# ssr_board.net
KiCad netlist of a schematic drawn in EAGLE
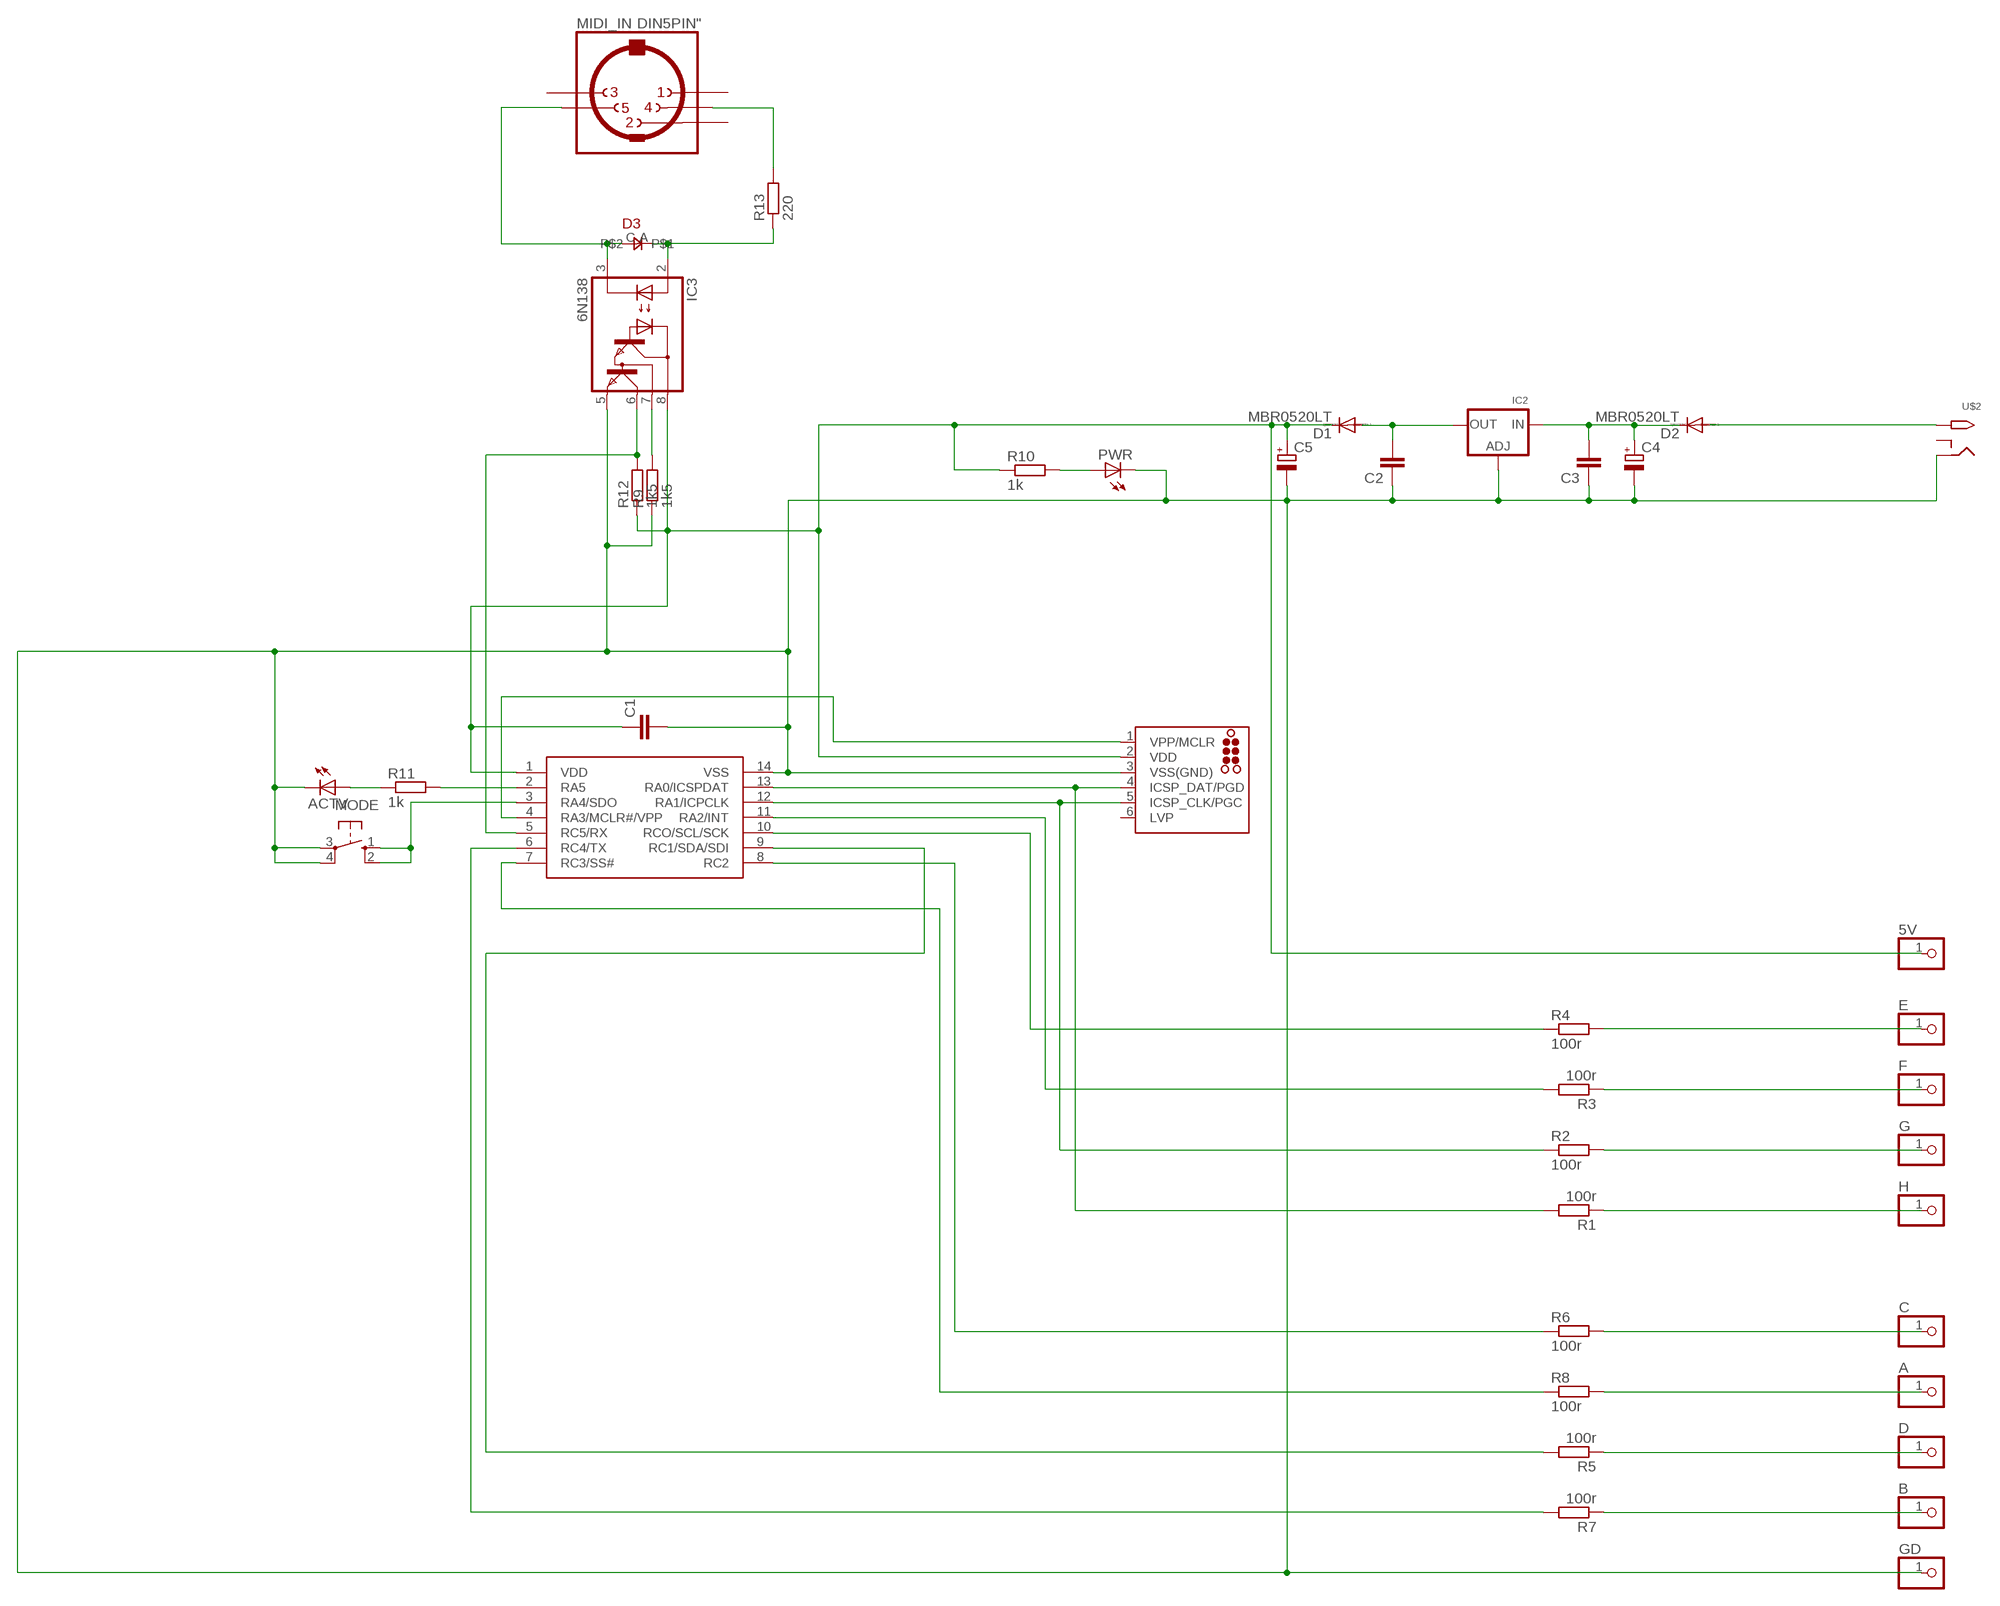
[diagram p0: schematic, sheet 1]

(export (version "E")
  (design (tool "Eeschema 10.0.6"))
  (components
    (comp (ref "5V")
      (value "PINHD-1X1")
      (footprint "eagle-import:1X01")
      (libsource (lib "eagle-import") (part "PINHD-1X1"))
    )
    (comp (ref "A")
      (value "PINHD-1X1")
      (footprint "eagle-import:1X01")
      (libsource (lib "eagle-import") (part "PINHD-1X1"))
    )
    (comp (ref "ACTV")
      (value "LED3MM")
      (footprint "eagle-import:LED3MM")
      (libsource (lib "eagle-import") (part "LED3MM"))
    )
    (comp (ref "B")
      (value "PINHD-1X1")
      (footprint "eagle-import:1X01")
      (libsource (lib "eagle-import") (part "PINHD-1X1"))
    )
    (comp (ref "C")
      (value "PINHD-1X1")
      (footprint "eagle-import:1X01")
      (libsource (lib "eagle-import") (part "PINHD-1X1"))
    )
    (comp (ref "C1")
      (value "C-EUC0805")
      (footprint "eagle-import:C0805")
      (libsource (lib "eagle-import") (part "C-EUC0805"))
    )
    (comp (ref "C2")
      (value "C-EUC0805")
      (footprint "eagle-import:C0805")
      (libsource (lib "eagle-import") (part "C-EUC0805"))
    )
    (comp (ref "C3")
      (value "C-EUC0805")
      (footprint "eagle-import:C0805")
      (libsource (lib "eagle-import") (part "C-EUC0805"))
    )
    (comp (ref "C4")
      (value "CPOL-EUE2-5")
      (footprint "eagle-import:E2-5")
      (libsource (lib "eagle-import") (part "CPOL-EUE2-5"))
    )
    (comp (ref "C5")
      (value "CPOL-EUE2-5")
      (footprint "eagle-import:E2-5")
      (libsource (lib "eagle-import") (part "CPOL-EUE2-5"))
    )
    (comp (ref "D")
      (value "PINHD-1X1")
      (footprint "eagle-import:1X01")
      (libsource (lib "eagle-import") (part "PINHD-1X1"))
    )
    (comp (ref "D1")
      (value "MBR0520LT")
      (footprint "eagle-import:SOD123")
      (libsource (lib "eagle-import") (part "MBR0520LT"))
    )
    (comp (ref "D2")
      (value "MBR0520LT")
      (footprint "eagle-import:SOD123")
      (libsource (lib "eagle-import") (part "MBR0520LT"))
    )
    (comp (ref "D3")
      (value "0805DIODE")
      (footprint "eagle-import:0805DIODE")
      (libsource (lib "eagle-import") (part "0805DIODE"))
    )
    (comp (ref "E")
      (value "PINHD-1X1")
      (footprint "eagle-import:1X01")
      (libsource (lib "eagle-import") (part "PINHD-1X1"))
    )
    (comp (ref "F")
      (value "PINHD-1X1")
      (footprint "eagle-import:1X01")
      (libsource (lib "eagle-import") (part "PINHD-1X1"))
    )
    (comp (ref "G")
      (value "PINHD-1X1")
      (footprint "eagle-import:1X01")
      (libsource (lib "eagle-import") (part "PINHD-1X1"))
    )
    (comp (ref "GD")
      (value "PINHD-1X1")
      (footprint "eagle-import:1X01")
      (libsource (lib "eagle-import") (part "PINHD-1X1"))
    )
    (comp (ref "H")
      (value "PINHD-1X1")
      (footprint "eagle-import:1X01")
      (libsource (lib "eagle-import") (part "PINHD-1X1"))
    )
    (comp (ref "IC1")
      (value "PIC16F1825SO14")
      (footprint "eagle-import:SO14")
      (libsource (lib "eagle-import") (part "PIC16F1825SO14"))
    )
    (comp (ref "IC2")
      (value "LM1117SOT223-WAVE")
      (footprint "eagle-import:SOT223-W")
      (libsource (lib "eagle-import") (part "LM1117SOT223-WAVE"))
    )
    (comp (ref "IC3")
      (value "6N138")
      (footprint "eagle-import:DIL08")
      (libsource (lib "eagle-import") (part "6N138"))
    )
    (comp (ref "ICSP")
      (value "TC2030-MCP-NL")
      (footprint "eagle-import:TC2030-MCP-NL")
      (libsource (lib "eagle-import") (part "TC2030-MCP-NL"))
    )
    (comp (ref "MIDI_IN")
      (value "DIN5PIN\"")
      (footprint "eagle-import:TRUCONN90")
      (libsource (lib "eagle-import") (part "DIN5PIN{dblquote}"))
    )
    (comp (ref "MODE")
      (value "10-XX")
      (footprint "eagle-import:B3F-10XX")
      (libsource (lib "eagle-import") (part "10-XX"))
    )
    (comp (ref "PWR")
      (value "LED3MM")
      (footprint "eagle-import:LED3MM")
      (libsource (lib "eagle-import") (part "LED3MM"))
    )
    (comp (ref "R1")
      (value "100r")
      (footprint "eagle-import:R0805")
      (libsource (lib "eagle-import") (part "R-EU_R0805"))
    )
    (comp (ref "R2")
      (value "100r")
      (footprint "eagle-import:R0805")
      (libsource (lib "eagle-import") (part "R-EU_R0805"))
    )
    (comp (ref "R3")
      (value "100r")
      (footprint "eagle-import:R0805")
      (libsource (lib "eagle-import") (part "R-EU_R0805"))
    )
    (comp (ref "R4")
      (value "100r")
      (footprint "eagle-import:R0805")
      (libsource (lib "eagle-import") (part "R-EU_R0805"))
    )
    (comp (ref "R5")
      (value "100r")
      (footprint "eagle-import:R0805")
      (libsource (lib "eagle-import") (part "R-EU_R0805"))
    )
    (comp (ref "R6")
      (value "100r")
      (footprint "eagle-import:R0805")
      (libsource (lib "eagle-import") (part "R-EU_R0805"))
    )
    (comp (ref "R7")
      (value "100r")
      (footprint "eagle-import:R0805")
      (libsource (lib "eagle-import") (part "R-EU_R0805"))
    )
    (comp (ref "R8")
      (value "100r")
      (footprint "eagle-import:R0805")
      (libsource (lib "eagle-import") (part "R-EU_R0805"))
    )
    (comp (ref "R9")
      (value "1k5")
      (footprint "eagle-import:R0805")
      (libsource (lib "eagle-import") (part "R-EU_R0805"))
    )
    (comp (ref "R10")
      (value "1k")
      (footprint "eagle-import:R0805")
      (libsource (lib "eagle-import") (part "R-EU_R0805"))
    )
    (comp (ref "R11")
      (value "1k")
      (footprint "eagle-import:R0805")
      (libsource (lib "eagle-import") (part "R-EU_R0805"))
    )
    (comp (ref "R12")
      (value "1k5")
      (footprint "eagle-import:R0805")
      (libsource (lib "eagle-import") (part "R-EU_R0805"))
    )
    (comp (ref "R13")
      (value "220")
      (footprint "eagle-import:R0805")
      (libsource (lib "eagle-import") (part "R-EU_R0805"))
    )
    (comp (ref "U$2")
      (value "2.1MMJACKTHM")
      (footprint "eagle-import:PJ-102A")
      (libsource (lib "eagle-import") (part "2.1MMJACKTHM"))
    )
  )
  (nets
    (net (code "1") (name "Net-(A-Pad1)") (class "Default")
      (node (ref "A") (pin "1") (pinfunction "1_1") (pintype "passive"))
      (node (ref "R8") (pin "2") (pinfunction "2_2") (pintype "passive"))
    )
    (net (code "2") (name "Net-(ACTV-C)") (class "Default")
      (node (ref "ACTV") (pin "K") (pinfunction "C_K") (pintype "passive"))
      (node (ref "C1") (pin "2") (pinfunction "2_2") (pintype "passive"))
      (node (ref "C2") (pin "1") (pinfunction "1_1") (pintype "passive"))
      (node (ref "C3") (pin "1") (pinfunction "1_1") (pintype "passive"))
      (node (ref "C4") (pin "-") (pinfunction "-_-") (pintype "passive"))
      (node (ref "C5") (pin "-") (pinfunction "-_-") (pintype "passive"))
      (node (ref "GD") (pin "1") (pinfunction "1_1") (pintype "passive"))
      (node (ref "IC1") (pin "14") (pinfunction "VSS_14") (pintype "power_in"))
      (node (ref "IC2") (pin "1") (pinfunction "ADJ_1") (pintype "input"))
      (node (ref "IC3") (pin "5") (pinfunction "GND_5") (pintype "passive"))
      (node (ref "ICSP") (pin "3") (pinfunction "VSS(GND)_3") (pintype "power_in"))
      (node (ref "MODE") (pin "3") (pinfunction "P_3") (pintype "passive"))
      (node (ref "MODE") (pin "4") (pinfunction "P1_4") (pintype "passive"))
      (node (ref "PWR") (pin "K") (pinfunction "C_K") (pintype "passive"))
      (node (ref "R9") (pin "1") (pinfunction "1_1") (pintype "passive"))
      (node (ref "U$2") (pin "RING") (pinfunction "RING_RING") (pintype "bidirectional"))
    )
    (net (code "3") (name "Net-(ACTV-PadA)") (class "Default")
      (node (ref "ACTV") (pin "A") (pinfunction "A_A") (pintype "passive"))
      (node (ref "R11") (pin "1") (pinfunction "1_1") (pintype "passive"))
    )
    (net (code "4") (name "Net-(B-Pad1)") (class "Default")
      (node (ref "B") (pin "1") (pinfunction "1_1") (pintype "passive"))
      (node (ref "R7") (pin "1") (pinfunction "1_1") (pintype "passive"))
    )
    (net (code "5") (name "Net-(C-Pad1)") (class "Default")
      (node (ref "C") (pin "1") (pinfunction "1_1") (pintype "passive"))
      (node (ref "R6") (pin "2") (pinfunction "2_2") (pintype "passive"))
    )
    (net (code "6") (name "Net-(D-Pad1)") (class "Default")
      (node (ref "D") (pin "1") (pinfunction "1_1") (pintype "passive"))
      (node (ref "R5") (pin "1") (pinfunction "1_1") (pintype "passive"))
    )
    (net (code "7") (name "Net-(D2-PadA)") (class "Default")
      (node (ref "D2") (pin "A") (pinfunction "A_A") (pintype "passive"))
      (node (ref "U$2") (pin "TIP") (pinfunction "TIP_TIP") (pintype "bidirectional"))
    )
    (net (code "8") (name "Net-(D3-P$1)") (class "Default")
      (node (ref "D3") (pin "C") (pinfunction "P$1_C") (pintype "bidirectional"))
      (node (ref "IC3") (pin "3") (pinfunction "C_3") (pintype "passive"))
      (node (ref "MIDI_IN") (pin "5") (pinfunction "5_5") (pintype "passive"))
    )
    (net (code "9") (name "Net-(D3-P$2)") (class "Default")
      (node (ref "D3") (pin "A") (pinfunction "P$2_A") (pintype "bidirectional"))
      (node (ref "IC3") (pin "2") (pinfunction "A_2") (pintype "passive"))
      (node (ref "R13") (pin "1") (pinfunction "1_1") (pintype "passive"))
    )
    (net (code "10") (name "Net-(E-Pad1)") (class "Default")
      (node (ref "E") (pin "1") (pinfunction "1_1") (pintype "passive"))
      (node (ref "R4") (pin "2") (pinfunction "2_2") (pintype "passive"))
    )
    (net (code "11") (name "Net-(F-Pad1)") (class "Default")
      (node (ref "F") (pin "1") (pinfunction "1_1") (pintype "passive"))
      (node (ref "R3") (pin "1") (pinfunction "1_1") (pintype "passive"))
    )
    (net (code "12") (name "Net-(G-Pad1)") (class "Default")
      (node (ref "G") (pin "1") (pinfunction "1_1") (pintype "passive"))
      (node (ref "R2") (pin "2") (pinfunction "2_2") (pintype "passive"))
    )
    (net (code "13") (name "Net-(H-Pad1)") (class "Default")
      (node (ref "H") (pin "1") (pinfunction "1_1") (pintype "passive"))
      (node (ref "R1") (pin "1") (pinfunction "1_1") (pintype "passive"))
    )
    (net (code "14") (name "Net-(IC1-RA0{slash}ICSPDAT)") (class "Default")
      (node (ref "IC1") (pin "13") (pinfunction "RA0/ICSPDAT_13") (pintype "bidirectional"))
      (node (ref "ICSP") (pin "4") (pinfunction "ICSP_DAT/PGD_4") (pintype "bidirectional"))
      (node (ref "R1") (pin "2") (pinfunction "2_2") (pintype "passive"))
    )
    (net (code "15") (name "Net-(IC1-RA1{slash}ICPCLK)") (class "Default")
      (node (ref "IC1") (pin "12") (pinfunction "RA1/ICPCLK_12") (pintype "bidirectional"))
      (node (ref "ICSP") (pin "5") (pinfunction "ICSP_CLK/PGC_5") (pintype "output"))
      (node (ref "R2") (pin "1") (pinfunction "1_1") (pintype "passive"))
    )
    (net (code "16") (name "Net-(IC1-RA2{slash}INT)") (class "Default")
      (node (ref "IC1") (pin "11") (pinfunction "RA2/INT_11") (pintype "bidirectional"))
      (node (ref "R3") (pin "2") (pinfunction "2_2") (pintype "passive"))
    )
    (net (code "17") (name "Net-(IC1-RA3{slash}MCLR#{slash}VPP)") (class "Default")
      (node (ref "IC1") (pin "4") (pinfunction "RA3/MCLR#/VPP_4") (pintype "input"))
      (node (ref "ICSP") (pin "1") (pinfunction "VPP/MCLR_1") (pintype "passive"))
    )
    (net (code "18") (name "Net-(IC1-RA4{slash}SDO)") (class "Default")
      (node (ref "IC1") (pin "3") (pinfunction "RA4/SDO_3") (pintype "bidirectional"))
      (node (ref "MODE") (pin "1") (pinfunction "S_1") (pintype "passive"))
      (node (ref "MODE") (pin "2") (pinfunction "S1_2") (pintype "passive"))
    )
    (net (code "19") (name "Net-(IC1-RA5)") (class "Default")
      (node (ref "IC1") (pin "2") (pinfunction "RA5_2") (pintype "bidirectional"))
      (node (ref "R11") (pin "2") (pinfunction "2_2") (pintype "passive"))
    )
    (net (code "20") (name "Net-(IC1-RC1{slash}SDA{slash}SDI)") (class "Default")
      (node (ref "IC1") (pin "9") (pinfunction "RC1/SDA/SDI_9") (pintype "bidirectional"))
      (node (ref "R5") (pin "2") (pinfunction "2_2") (pintype "passive"))
    )
    (net (code "21") (name "Net-(IC1-RC2)") (class "Default")
      (node (ref "IC1") (pin "8") (pinfunction "RC2_8") (pintype "bidirectional"))
      (node (ref "R6") (pin "1") (pinfunction "1_1") (pintype "passive"))
    )
    (net (code "22") (name "Net-(IC1-RC3{slash}SS#)") (class "Default")
      (node (ref "IC1") (pin "7") (pinfunction "RC3/SS#_7") (pintype "bidirectional"))
      (node (ref "R8") (pin "1") (pinfunction "1_1") (pintype "passive"))
    )
    (net (code "23") (name "Net-(IC1-RC4{slash}TX)") (class "Default")
      (node (ref "IC1") (pin "6") (pinfunction "RC4/TX_6") (pintype "bidirectional"))
      (node (ref "R7") (pin "2") (pinfunction "2_2") (pintype "passive"))
    )
    (net (code "24") (name "Net-(IC1-RC5{slash}RX)") (class "Default")
      (node (ref "IC1") (pin "5") (pinfunction "RC5/RX_5") (pintype "bidirectional"))
      (node (ref "IC3") (pin "6") (pinfunction "VO_6") (pintype "passive"))
      (node (ref "R12") (pin "2") (pinfunction "2_2") (pintype "passive"))
    )
    (net (code "25") (name "Net-(IC1-RCO{slash}SCL{slash}SCK)") (class "Default")
      (node (ref "IC1") (pin "10") (pinfunction "RCO/SCL/SCK_10") (pintype "bidirectional"))
      (node (ref "R4") (pin "1") (pinfunction "1_1") (pintype "passive"))
    )
    (net (code "26") (name "Net-(IC1-VDD)") (class "Default")
      (node (ref "5V") (pin "1") (pinfunction "1_1") (pintype "passive"))
      (node (ref "C1") (pin "1") (pinfunction "1_1") (pintype "passive"))
      (node (ref "C5") (pin "+") (pinfunction "+_+") (pintype "passive"))
      (node (ref "D1") (pin "C") (pinfunction "C_C") (pintype "passive"))
      (node (ref "IC1") (pin "1") (pinfunction "VDD_1") (pintype "power_in"))
      (node (ref "IC3") (pin "8") (pinfunction "VCC_8") (pintype "passive"))
      (node (ref "ICSP") (pin "2") (pinfunction "VDD_2") (pintype "power_in"))
      (node (ref "R10") (pin "1") (pinfunction "1_1") (pintype "passive"))
      (node (ref "R12") (pin "1") (pinfunction "1_1") (pintype "passive"))
    )
    (net (code "27") (name "Net-(IC2-IN)") (class "Default")
      (node (ref "C3") (pin "2") (pinfunction "2_2") (pintype "passive"))
      (node (ref "C4") (pin "+") (pinfunction "+_+") (pintype "passive"))
      (node (ref "D2") (pin "C") (pinfunction "C_C") (pintype "passive"))
      (node (ref "IC2") (pin "3") (pinfunction "IN_3") (pintype "input"))
    )
    (net (code "28") (name "Net-(IC2-OUT)") (class "Default")
      (node (ref "C2") (pin "2") (pinfunction "2_2") (pintype "passive"))
      (node (ref "D1") (pin "A") (pinfunction "A_A") (pintype "passive"))
      (node (ref "IC2") (pin "2") (pinfunction "OUT_2") (pintype "passive"))
    )
    (net (code "29") (name "Net-(IC3-VB)") (class "Default")
      (node (ref "IC3") (pin "7") (pinfunction "VB_7") (pintype "passive"))
      (node (ref "R9") (pin "2") (pinfunction "2_2") (pintype "passive"))
    )
    (net (code "30") (name "Net-(MIDI_IN-Pad4)") (class "Default")
      (node (ref "MIDI_IN") (pin "4") (pinfunction "4_4") (pintype "passive"))
      (node (ref "R13") (pin "2") (pinfunction "2_2") (pintype "passive"))
    )
    (net (code "31") (name "Net-(PWR-PadA)") (class "Default")
      (node (ref "PWR") (pin "A") (pinfunction "A_A") (pintype "passive"))
      (node (ref "R10") (pin "2") (pinfunction "2_2") (pintype "passive"))
    )
    (net (code "32") (name "unconnected-(ICSP-LVP-Pad6)") (class "Default")
      (node (ref "ICSP") (pin "6") (pinfunction "LVP_6") (pintype "bidirectional"))
    )
    (net (code "33") (name "unconnected-(MIDI_IN-Pad1)") (class "Default")
      (node (ref "MIDI_IN") (pin "1") (pinfunction "1_1") (pintype "passive"))
    )
    (net (code "34") (name "unconnected-(MIDI_IN-Pad2)") (class "Default")
      (node (ref "MIDI_IN") (pin "2") (pinfunction "2_2") (pintype "passive"))
    )
    (net (code "35") (name "unconnected-(MIDI_IN-Pad3)") (class "Default")
      (node (ref "MIDI_IN") (pin "3") (pinfunction "3_3") (pintype "passive"))
    )
    (net (code "36") (name "unconnected-(U$2-PadRING_SW)") (class "Default")
      (node (ref "U$2") (pin "RING_SW") (pinfunction "RING_SW_RING_SW") (pintype "bidirectional"))
    )
  )
)
